# Sensor.net
KiCad netlist of a schematic drawn in EAGLE
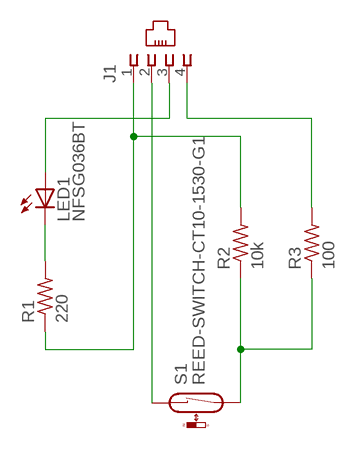
[diagram p0: schematic, sheet 1]

(export (version "E")
  (design (tool "Eeschema 10.0.6"))
  (components
    (comp (ref "J1")
      (value "555166-3")
      (footprint "eagle-import:555166-3")
      (libsource (lib "eagle-import") (part "555166-3"))
    )
    (comp (ref "LED1")
      (value "NFSG036BT")
      (footprint "eagle-import:NFSG036BT")
      (libsource (lib "eagle-import") (part "NFSG036BT"))
    )
    (comp (ref "R1")
      (value "220")
      (footprint "eagle-import:R0603")
      (libsource (lib "eagle-import") (part "R-US_R0603"))
    )
    (comp (ref "R2")
      (value "10k")
      (footprint "eagle-import:R0603")
      (libsource (lib "eagle-import") (part "R-US_R0603"))
    )
    (comp (ref "R3")
      (value "100")
      (footprint "eagle-import:R0603")
      (libsource (lib "eagle-import") (part "R-US_R0603"))
    )
    (comp (ref "S1")
      (value "REED-SWITCH-CT10-1530-G1")
      (footprint "eagle-import:CT10-G1")
      (fields (field (name "MF") "COTO TECHNOLOGY") (field (name "MPN") "CT10-1530-G1"))
      (libsource (lib "eagle-import") (part "REED-SWITCH-CT10-1530-G1"))
    )
  )
  (nets
    (net (code "1") (name "Net-(J1-Pad1)") (class "Default")
      (node (ref "J1") (pin "1") (pinfunction "1_1") (pintype "passive"))
      (node (ref "R1") (pin "1") (pinfunction "1_1") (pintype "passive"))
      (node (ref "R2") (pin "2") (pinfunction "2_2") (pintype "passive"))
    )
    (net (code "2") (name "Net-(J1-Pad2)") (class "Default")
      (node (ref "J1") (pin "2") (pinfunction "2_2") (pintype "passive"))
      (node (ref "S1") (pin "1") (pinfunction "1_1") (pintype "passive"))
    )
    (net (code "3") (name "Net-(J1-Pad3)") (class "Default")
      (node (ref "J1") (pin "3") (pinfunction "3_3") (pintype "passive"))
      (node (ref "LED1") (pin "A") (pinfunction "A_A") (pintype "passive"))
    )
    (net (code "4") (name "Net-(J1-Pad4)") (class "Default")
      (node (ref "J1") (pin "4") (pinfunction "4_4") (pintype "passive"))
      (node (ref "R3") (pin "2") (pinfunction "2_2") (pintype "passive"))
    )
    (net (code "5") (name "Net-(LED1-PadC)") (class "Default")
      (node (ref "LED1") (pin "C") (pinfunction "C_C") (pintype "passive"))
      (node (ref "R1") (pin "2") (pinfunction "2_2") (pintype "passive"))
    )
    (net (code "6") (name "Net-(R2-Pad1)") (class "Default")
      (node (ref "R2") (pin "1") (pinfunction "1_1") (pintype "passive"))
      (node (ref "R3") (pin "1") (pinfunction "1_1") (pintype "passive"))
      (node (ref "S1") (pin "2") (pinfunction "2_2") (pintype "passive"))
    )
  )
)
